# keypad_0_1.net
KiCad netlist of a schematic drawn in EAGLE
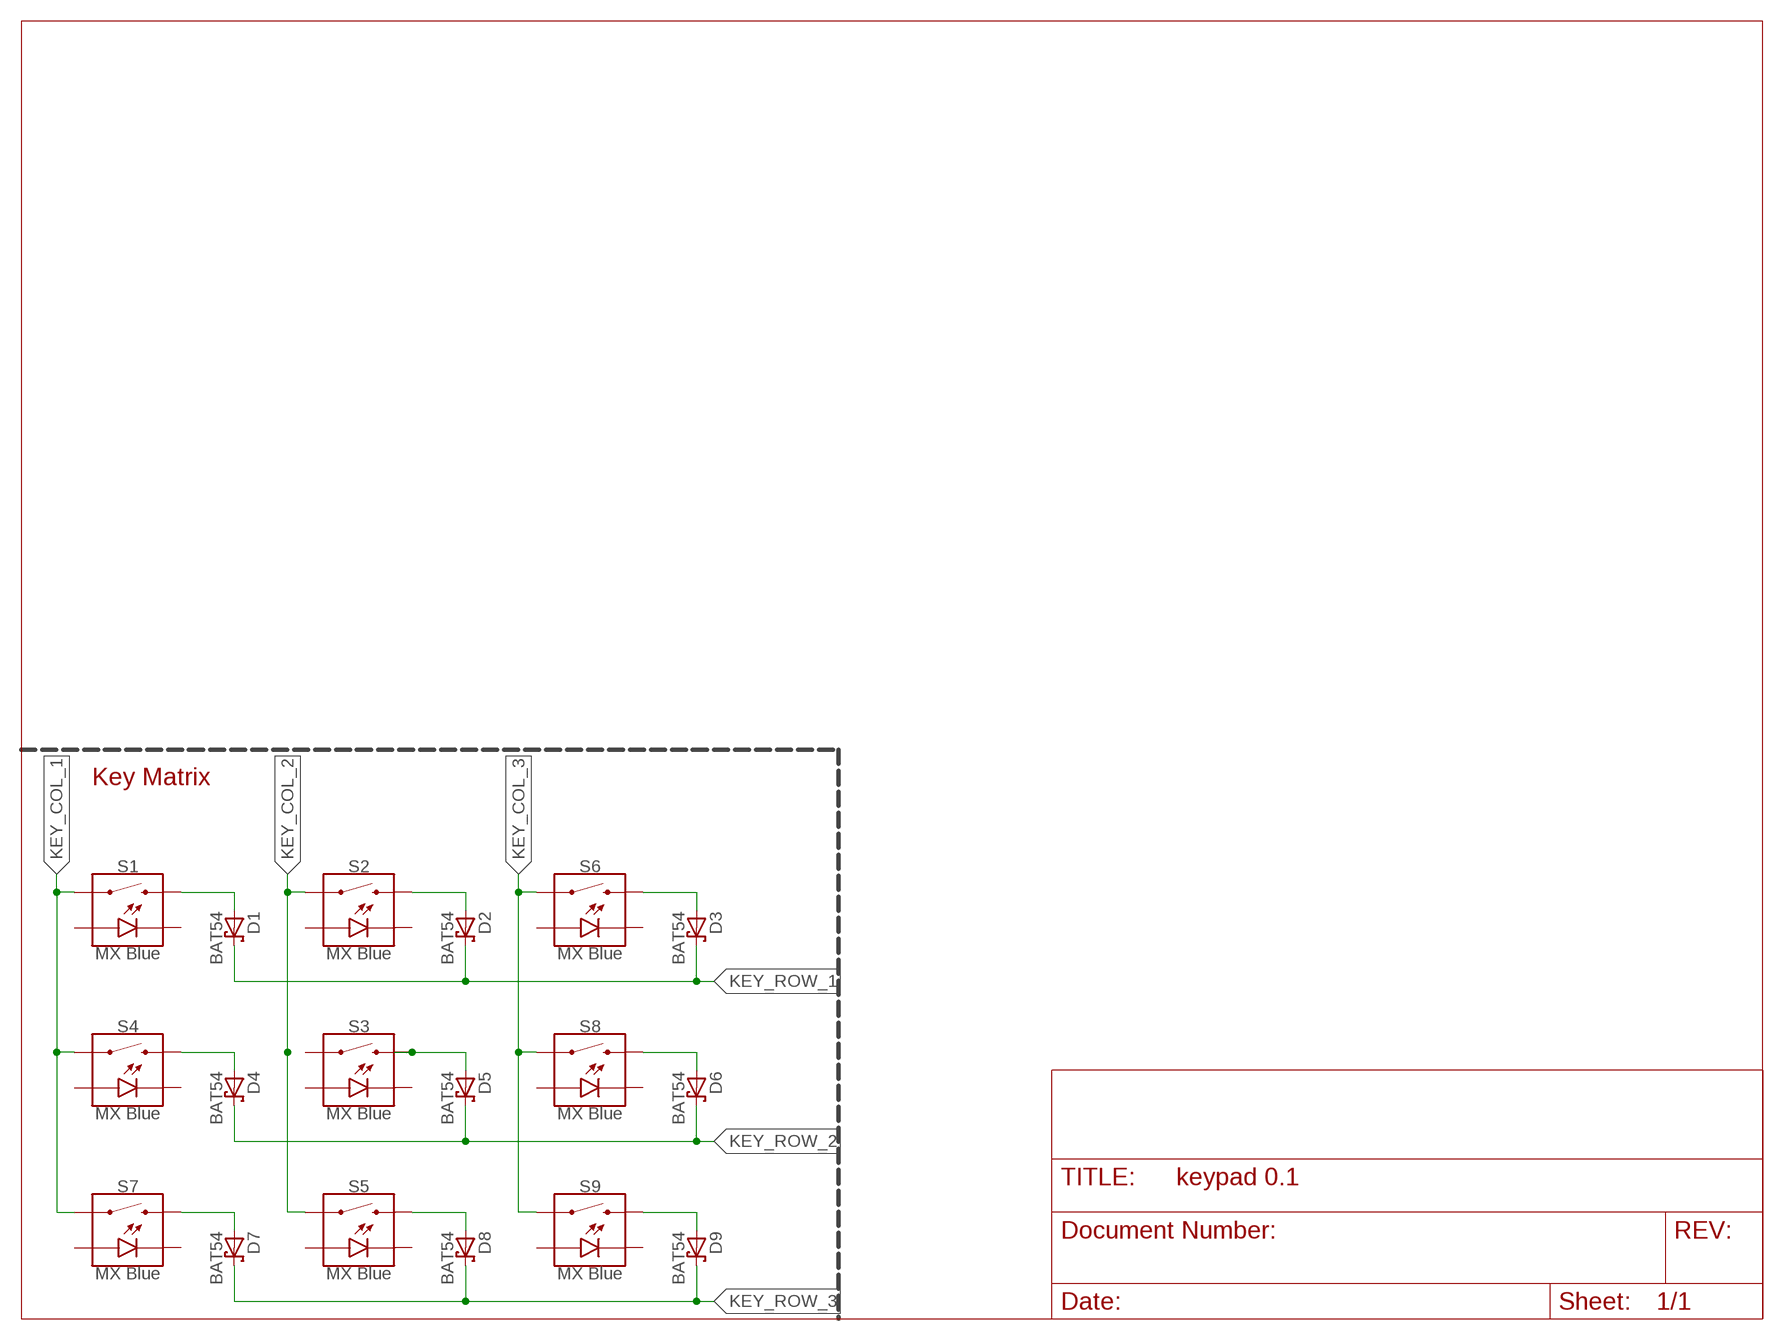
[diagram p0: schematic, sheet 1]

(export (version "E")
  (design (tool "Eeschema 10.0.6"))
  (components
    (comp (ref "D1")
      (value "BAT54")
      (footprint "eagle-import:SOT23")
      (libsource (lib "eagle-import") (part "BAT54"))
    )
    (comp (ref "D2")
      (value "BAT54")
      (footprint "eagle-import:SOT23")
      (libsource (lib "eagle-import") (part "BAT54"))
    )
    (comp (ref "D3")
      (value "BAT54")
      (footprint "eagle-import:SOT23")
      (libsource (lib "eagle-import") (part "BAT54"))
    )
    (comp (ref "D4")
      (value "BAT54")
      (footprint "eagle-import:SOT23")
      (libsource (lib "eagle-import") (part "BAT54"))
    )
    (comp (ref "D5")
      (value "BAT54")
      (footprint "eagle-import:SOT23")
      (libsource (lib "eagle-import") (part "BAT54"))
    )
    (comp (ref "D6")
      (value "BAT54")
      (footprint "eagle-import:SOT23")
      (libsource (lib "eagle-import") (part "BAT54"))
    )
    (comp (ref "D7")
      (value "BAT54")
      (footprint "eagle-import:SOT23")
      (libsource (lib "eagle-import") (part "BAT54"))
    )
    (comp (ref "D8")
      (value "BAT54")
      (footprint "eagle-import:SOT23")
      (libsource (lib "eagle-import") (part "BAT54"))
    )
    (comp (ref "D9")
      (value "BAT54")
      (footprint "eagle-import:SOT23")
      (libsource (lib "eagle-import") (part "BAT54"))
    )
    (comp (ref "S1")
      (value "MX Blue")
      (footprint "eagle-import:CHERRY-MX-LED")
      (libsource (lib "eagle-import") (part "MOMENTARY-SWITCH-SPST-LED-PTH-CHERRY"))
    )
    (comp (ref "S2")
      (value "MX Blue")
      (footprint "eagle-import:CHERRY-MX-LED")
      (libsource (lib "eagle-import") (part "MOMENTARY-SWITCH-SPST-LED-PTH-CHERRY"))
    )
    (comp (ref "S3")
      (value "MX Blue")
      (footprint "eagle-import:CHERRY-MX-LED")
      (libsource (lib "eagle-import") (part "MOMENTARY-SWITCH-SPST-LED-PTH-CHERRY"))
    )
    (comp (ref "S4")
      (value "MX Blue")
      (footprint "eagle-import:CHERRY-MX-LED")
      (libsource (lib "eagle-import") (part "MOMENTARY-SWITCH-SPST-LED-PTH-CHERRY"))
    )
    (comp (ref "S5")
      (value "MX Blue")
      (footprint "eagle-import:CHERRY-MX-LED")
      (libsource (lib "eagle-import") (part "MOMENTARY-SWITCH-SPST-LED-PTH-CHERRY"))
    )
    (comp (ref "S6")
      (value "MX Blue")
      (footprint "eagle-import:CHERRY-MX-LED")
      (libsource (lib "eagle-import") (part "MOMENTARY-SWITCH-SPST-LED-PTH-CHERRY"))
    )
    (comp (ref "S7")
      (value "MX Blue")
      (footprint "eagle-import:CHERRY-MX-LED")
      (libsource (lib "eagle-import") (part "MOMENTARY-SWITCH-SPST-LED-PTH-CHERRY"))
    )
    (comp (ref "S8")
      (value "MX Blue")
      (footprint "eagle-import:CHERRY-MX-LED")
      (libsource (lib "eagle-import") (part "MOMENTARY-SWITCH-SPST-LED-PTH-CHERRY"))
    )
    (comp (ref "S9")
      (value "MX Blue")
      (footprint "eagle-import:CHERRY-MX-LED")
      (libsource (lib "eagle-import") (part "MOMENTARY-SWITCH-SPST-LED-PTH-CHERRY"))
    )
  )
  (nets
    (net (code "1") (name "KEY_COL_1") (class "Default")
      (node (ref "S1") (pin "S1") (pinfunction "1_S1") (pintype "passive"))
      (node (ref "S4") (pin "S1") (pinfunction "1_S1") (pintype "passive"))
      (node (ref "S7") (pin "S1") (pinfunction "1_S1") (pintype "passive"))
    )
    (net (code "2") (name "KEY_COL_2") (class "Default")
      (node (ref "S2") (pin "S1") (pinfunction "1_S1") (pintype "passive"))
      (node (ref "S5") (pin "S1") (pinfunction "1_S1") (pintype "passive"))
    )
    (net (code "3") (name "KEY_COL_3") (class "Default")
      (node (ref "S6") (pin "S1") (pinfunction "1_S1") (pintype "passive"))
      (node (ref "S8") (pin "S1") (pinfunction "1_S1") (pintype "passive"))
      (node (ref "S9") (pin "S1") (pinfunction "1_S1") (pintype "passive"))
    )
    (net (code "4") (name "KEY_ROW_1") (class "Default")
      (node (ref "D1") (pin "3") (pinfunction "C_3") (pintype "passive"))
      (node (ref "D2") (pin "3") (pinfunction "C_3") (pintype "passive"))
      (node (ref "D3") (pin "3") (pinfunction "C_3") (pintype "passive"))
    )
    (net (code "5") (name "KEY_ROW_2") (class "Default")
      (node (ref "D4") (pin "3") (pinfunction "C_3") (pintype "passive"))
      (node (ref "D5") (pin "3") (pinfunction "C_3") (pintype "passive"))
      (node (ref "D6") (pin "3") (pinfunction "C_3") (pintype "passive"))
    )
    (net (code "6") (name "KEY_ROW_3") (class "Default")
      (node (ref "D7") (pin "3") (pinfunction "C_3") (pintype "passive"))
      (node (ref "D8") (pin "3") (pinfunction "C_3") (pintype "passive"))
      (node (ref "D9") (pin "3") (pinfunction "C_3") (pintype "passive"))
    )
    (net (code "7") (name "Net-(D1-A)") (class "Default")
      (node (ref "D1") (pin "1") (pinfunction "A_1") (pintype "passive"))
      (node (ref "S1") (pin "S2") (pinfunction "2_S2") (pintype "passive"))
    )
    (net (code "8") (name "Net-(D2-A)") (class "Default")
      (node (ref "D2") (pin "1") (pinfunction "A_1") (pintype "passive"))
      (node (ref "S2") (pin "S2") (pinfunction "2_S2") (pintype "passive"))
    )
    (net (code "9") (name "Net-(D3-A)") (class "Default")
      (node (ref "D3") (pin "1") (pinfunction "A_1") (pintype "passive"))
      (node (ref "S6") (pin "S2") (pinfunction "2_S2") (pintype "passive"))
    )
    (net (code "10") (name "Net-(D4-A)") (class "Default")
      (node (ref "D4") (pin "1") (pinfunction "A_1") (pintype "passive"))
      (node (ref "S4") (pin "S2") (pinfunction "2_S2") (pintype "passive"))
    )
    (net (code "11") (name "Net-(D5-A)") (class "Default")
      (node (ref "D5") (pin "1") (pinfunction "A_1") (pintype "passive"))
      (node (ref "S3") (pin "S2") (pinfunction "2_S2") (pintype "passive"))
    )
    (net (code "12") (name "Net-(D6-A)") (class "Default")
      (node (ref "D6") (pin "1") (pinfunction "A_1") (pintype "passive"))
      (node (ref "S8") (pin "S2") (pinfunction "2_S2") (pintype "passive"))
    )
    (net (code "13") (name "Net-(D7-A)") (class "Default")
      (node (ref "D7") (pin "1") (pinfunction "A_1") (pintype "passive"))
      (node (ref "S7") (pin "S2") (pinfunction "2_S2") (pintype "passive"))
    )
    (net (code "14") (name "Net-(D8-A)") (class "Default")
      (node (ref "D8") (pin "1") (pinfunction "A_1") (pintype "passive"))
      (node (ref "S5") (pin "S2") (pinfunction "2_S2") (pintype "passive"))
    )
    (net (code "15") (name "Net-(D9-A)") (class "Default")
      (node (ref "D9") (pin "1") (pinfunction "A_1") (pintype "passive"))
      (node (ref "S9") (pin "S2") (pinfunction "2_S2") (pintype "passive"))
    )
    (net (code "16") (name "unconnected-(S1-C-PadK)") (class "Default")
      (node (ref "S1") (pin "K") (pinfunction "C_K") (pintype "passive"))
    )
    (net (code "17") (name "unconnected-(S1-PadA)") (class "Default")
      (node (ref "S1") (pin "A") (pinfunction "A_A") (pintype "passive"))
    )
    (net (code "18") (name "unconnected-(S2-C-PadK)") (class "Default")
      (node (ref "S2") (pin "K") (pinfunction "C_K") (pintype "passive"))
    )
    (net (code "19") (name "unconnected-(S2-PadA)") (class "Default")
      (node (ref "S2") (pin "A") (pinfunction "A_A") (pintype "passive"))
    )
    (net (code "20") (name "unconnected-(S3-1-PadS1)") (class "Default")
      (node (ref "S3") (pin "S1") (pinfunction "1_S1") (pintype "passive"))
    )
    (net (code "21") (name "unconnected-(S3-C-PadK)") (class "Default")
      (node (ref "S3") (pin "K") (pinfunction "C_K") (pintype "passive"))
    )
    (net (code "22") (name "unconnected-(S3-PadA)") (class "Default")
      (node (ref "S3") (pin "A") (pinfunction "A_A") (pintype "passive"))
    )
    (net (code "23") (name "unconnected-(S4-C-PadK)") (class "Default")
      (node (ref "S4") (pin "K") (pinfunction "C_K") (pintype "passive"))
    )
    (net (code "24") (name "unconnected-(S4-PadA)") (class "Default")
      (node (ref "S4") (pin "A") (pinfunction "A_A") (pintype "passive"))
    )
    (net (code "25") (name "unconnected-(S5-C-PadK)") (class "Default")
      (node (ref "S5") (pin "K") (pinfunction "C_K") (pintype "passive"))
    )
    (net (code "26") (name "unconnected-(S5-PadA)") (class "Default")
      (node (ref "S5") (pin "A") (pinfunction "A_A") (pintype "passive"))
    )
    (net (code "27") (name "unconnected-(S6-C-PadK)") (class "Default")
      (node (ref "S6") (pin "K") (pinfunction "C_K") (pintype "passive"))
    )
    (net (code "28") (name "unconnected-(S6-PadA)") (class "Default")
      (node (ref "S6") (pin "A") (pinfunction "A_A") (pintype "passive"))
    )
    (net (code "29") (name "unconnected-(S7-C-PadK)") (class "Default")
      (node (ref "S7") (pin "K") (pinfunction "C_K") (pintype "passive"))
    )
    (net (code "30") (name "unconnected-(S7-PadA)") (class "Default")
      (node (ref "S7") (pin "A") (pinfunction "A_A") (pintype "passive"))
    )
    (net (code "31") (name "unconnected-(S8-C-PadK)") (class "Default")
      (node (ref "S8") (pin "K") (pinfunction "C_K") (pintype "passive"))
    )
    (net (code "32") (name "unconnected-(S8-PadA)") (class "Default")
      (node (ref "S8") (pin "A") (pinfunction "A_A") (pintype "passive"))
    )
    (net (code "33") (name "unconnected-(S9-C-PadK)") (class "Default")
      (node (ref "S9") (pin "K") (pinfunction "C_K") (pintype "passive"))
    )
    (net (code "34") (name "unconnected-(S9-PadA)") (class "Default")
      (node (ref "S9") (pin "A") (pinfunction "A_A") (pintype "passive"))
    )
  )
)
